# SPI_Stuff.net
KiCad netlist of a schematic drawn in Altium Designer
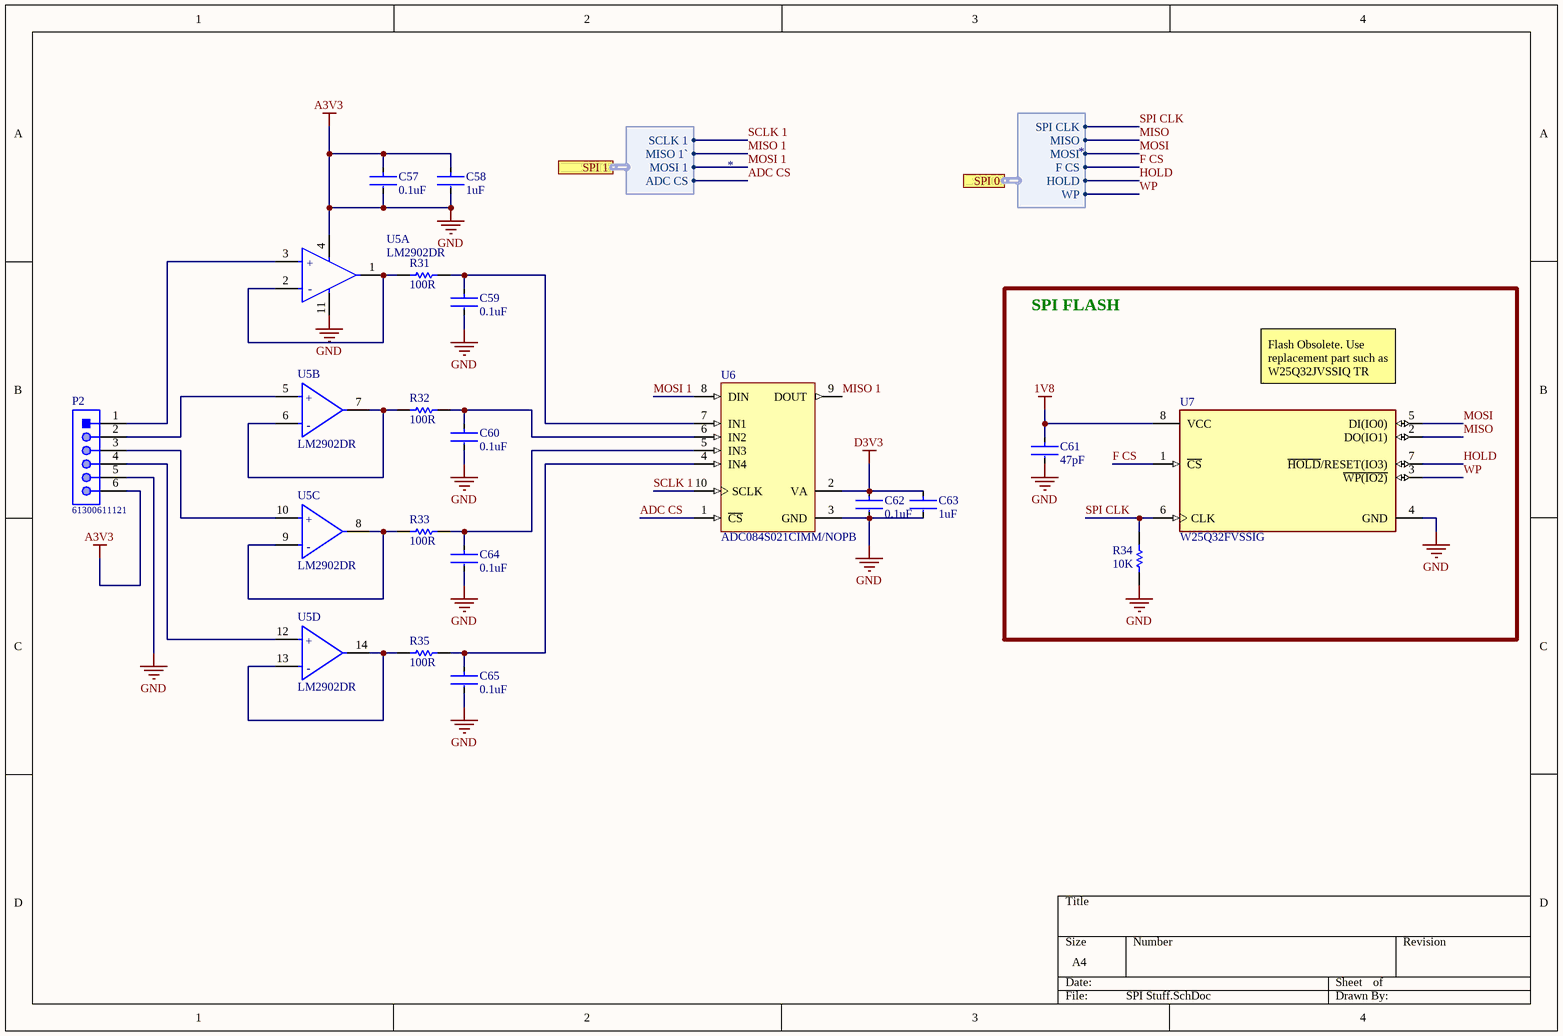
[diagram p0: SPI Stuff.SchDoc]

(export (version "E")
  (design (tool "Eeschema 10.0.6"))
  (components
    (comp (ref "C57")
      (value "0.1uF")
      (footprint "FP-GRM15-MFG")
      (description "CAP CER 0.1UF 16V X7R 0402")
      (fields (field (name "MANUFACTURER PART NUMBER") "GRM155R71C104KA88D") (field (name "TOLERANCE") "10%"))
      (libsource (lib "Altium Content Vault") (part "236180d848d6139a670b325ea6854c9"))
    )
    (comp (ref "C58")
      (value "1uF")
      (footprint "FP-GRM15-MFG")
      (description "CAP CER 0.1UF 16V X7R 0402")
      (fields (field (name "MANUFACTURER PART NUMBER") "GRM155R71C104KA88D") (field (name "TOLERANCE") "10%"))
      (libsource (lib "Altium Content Vault") (part "236180d848d6139a670b325ea6854c9"))
    )
    (comp (ref "C59")
      (value "0.1uF")
      (footprint "FP-GRM15-MFG")
      (description "CAP CER 0.1UF 16V X7R 0402")
      (fields (field (name "MANUFACTURER PART NUMBER") "GRM155R71C104KA88D") (field (name "TOLERANCE") "10%"))
      (libsource (lib "Altium Content Vault") (part "236180d848d6139a670b325ea6854c9"))
    )
    (comp (ref "C60")
      (value "0.1uF")
      (footprint "FP-GRM15-MFG")
      (description "CAP CER 0.1UF 16V X7R 0402")
      (fields (field (name "MANUFACTURER PART NUMBER") "GRM155R71C104KA88D") (field (name "TOLERANCE") "10%"))
      (libsource (lib "Altium Content Vault") (part "236180d848d6139a670b325ea6854c9"))
    )
    (comp (ref "C61")
      (value "47pF")
      (footprint "FP-GRM15-MFG")
      (description "CAP CER 0.1UF 16V X7R 0402")
      (fields (field (name "MANUFACTURER PART NUMBER") "GRM155R71C104KA88D") (field (name "TOLERANCE") "10%"))
      (libsource (lib "Altium Content Vault") (part "236180d848d6139a670b325ea6854c9"))
    )
    (comp (ref "C62")
      (value "0.1uF")
      (footprint "FP-GRM15-MFG")
      (description "CAP CER 0.1UF 16V X7R 0402")
      (fields (field (name "MANUFACTURER PART NUMBER") "GRM155R71C104KA88D") (field (name "TOLERANCE") "10%"))
      (libsource (lib "Altium Content Vault") (part "236180d848d6139a670b325ea6854c9"))
    )
    (comp (ref "C63")
      (value "1uF")
      (footprint "FP-GRM15-MFG")
      (description "CAP CER 0.1UF 16V X7R 0402")
      (fields (field (name "MANUFACTURER PART NUMBER") "GRM155R71C104KA88D") (field (name "TOLERANCE") "10%"))
      (libsource (lib "Altium Content Vault") (part "236180d848d6139a670b325ea6854c9"))
    )
    (comp (ref "C64")
      (value "0.1uF")
      (footprint "FP-GRM15-MFG")
      (description "CAP CER 0.1UF 16V X7R 0402")
      (fields (field (name "MANUFACTURER PART NUMBER") "GRM155R71C104KA88D") (field (name "TOLERANCE") "10%"))
      (libsource (lib "Altium Content Vault") (part "236180d848d6139a670b325ea6854c9"))
    )
    (comp (ref "C65")
      (value "0.1uF")
      (footprint "FP-GRM15-MFG")
      (description "CAP CER 0.1UF 16V X7R 0402")
      (fields (field (name "MANUFACTURER PART NUMBER") "GRM155R71C104KA88D") (field (name "TOLERANCE") "10%"))
      (libsource (lib "Altium Content Vault") (part "236180d848d6139a670b325ea6854c9"))
    )
    (comp (ref "P2")
      (value "61300611121")
      (footprint "61300611121")
      (description "THT Vertical Pin Header WR-PHD, Pitch 2.54 mm, Single Row, 6 pins")
      (fields (field (name "MANUFACTURER") "Wurth Elektronik") (field (name "PUBLISHER") "WurthElektronik"))
      (libsource (lib "Altium Content Vault") (part "WE-CN-1P-M-R6"))
    )
    (comp (ref "R31")
      (value "100R")
      (footprint "RESC1005X40X25LL05T05")
      (description "Chip Resistor, 0 Ohm, 0.1 W, -55 to 155 degC, 0402 (1005 Metric), RoHS, Tape and Reel")
      (fields (field (name "MANUFACTURER") "Panasonic") (field (name "TOLERANCE") "5%"))
      (libsource (lib "Altium Content Vault") (part "RES-2"))
    )
    (comp (ref "R32")
      (value "100R")
      (footprint "RESC1005X40X25LL05T05")
      (description "Chip Resistor, 0 Ohm, 0.1 W, -55 to 155 degC, 0402 (1005 Metric), RoHS, Tape and Reel")
      (fields (field (name "MANUFACTURER") "Panasonic") (field (name "TOLERANCE") "5%"))
      (libsource (lib "Altium Content Vault") (part "RES-2"))
    )
    (comp (ref "R33")
      (value "100R")
      (footprint "RESC1005X40X25LL05T05")
      (description "Chip Resistor, 0 Ohm, 0.1 W, -55 to 155 degC, 0402 (1005 Metric), RoHS, Tape and Reel")
      (fields (field (name "MANUFACTURER") "Panasonic") (field (name "TOLERANCE") "5%"))
      (libsource (lib "Altium Content Vault") (part "RES-2"))
    )
    (comp (ref "R34")
      (value "10K")
      (footprint "RESC1005X40X25LL05T05")
      (description "Chip Resistor, 0 Ohm, 0.1 W, -55 to 155 degC, 0402 (1005 Metric), RoHS, Tape and Reel")
      (fields (field (name "MANUFACTURER") "Panasonic") (field (name "TOLERANCE") "5%"))
      (libsource (lib "Altium Content Vault") (part "RES-2"))
    )
    (comp (ref "R35")
      (value "100R")
      (footprint "RESC1005X40X25LL05T05")
      (description "Chip Resistor, 0 Ohm, 0.1 W, -55 to 155 degC, 0402 (1005 Metric), RoHS, Tape and Reel")
      (fields (field (name "MANUFACTURER") "Panasonic") (field (name "TOLERANCE") "5%"))
      (libsource (lib "Altium Content Vault") (part "RES-2"))
    )
    (comp (ref "U5")
      (value "LM2902DR")
      (footprint "FP-D0014A-IPC_A")
      (description "IC OPAMP GP 4 CIRCUIT 14SOIC")
      (libsource (lib "Altium Content Vault") (part "b02d0cb41c0d90ddc6f34c0e90b5c12"))
    )
    (comp (ref "U6")
      (value "ADC084S021CIMM/NOPB")
      (footprint "MUB10A_N")
      (description "4 Channel, 50 kSPS to 200 kSPS, 8-Bit A/D Converter, 10-pin Mini SOIC, Pb-Free")
      (fields (field (name "MANUFACTURER") "National Semiconductor"))
      (libsource (lib "Altium Content Vault") (part "CON-ADC-ADC104S101CIMM"))
    )
    (comp (ref "U7")
      (value "W25Q32FVSSIG")
      (footprint "FP-SS-MFG")
      (description "IC FLASH 32M SPI 104MHZ 8SOIC")
      (fields
        (field (name "MANUFACTURER") "Winbond")
        (field (name "OCTOPART") "https://octopart.com/w25q32fvssig-winbond-23896462")
      )
      (libsource (lib "Altium Content Vault") (part "4804fbe011262506d6ec6a9051036b0"))
    )
  )
  (nets
    (net (code "2") (name "/ADC CS") (class "Default")
      (node (ref "U6") (pin "1") (pinfunction "~{CS}_1") (pintype "input"))
    )
    (net (code "3") (name "/F CS") (class "Default")
      (node (ref "U7") (pin "1") (pinfunction "~{CS}_1") (pintype "input"))
    )
    (net (code "4") (name "/HOLD") (class "Default")
      (node (ref "U7") (pin "7") (pinfunction "~{HOLD}/RESET(IO3)_7") (pintype "bidirectional"))
    )
    (net (code "5") (name "/MISO") (class "Default")
      (node (ref "U7") (pin "2") (pinfunction "DO(IO1)_2") (pintype "bidirectional"))
    )
    (net (code "6") (name "/MISO 1") (class "Default")
      (node (ref "U6") (pin "9") (pinfunction "DOUT_9") (pintype "output"))
    )
    (net (code "7") (name "/MOSI") (class "Default")
      (node (ref "U7") (pin "5") (pinfunction "DI(IO0)_5") (pintype "bidirectional"))
    )
    (net (code "8") (name "/MOSI 1") (class "Default")
      (node (ref "U6") (pin "8") (pinfunction "DIN_8") (pintype "input"))
    )
    (net (code "9") (name "/SCLK 1") (class "Default")
      (node (ref "U6") (pin "10") (pinfunction "SCLK_10") (pintype "input"))
    )
    (net (code "10") (name "/SPI CLK") (class "Default")
      (node (ref "R34") (pin "2") (pinfunction "2_2") (pintype "passive"))
      (node (ref "U7") (pin "6") (pinfunction "CLK_6") (pintype "input"))
    )
    (net (code "11") (name "/WP") (class "Default")
      (node (ref "U7") (pin "3") (pinfunction "~{WP(IO2)}_3") (pintype "bidirectional"))
    )
    (net (code "13") (name "1V8") (class "Default")
      (node (ref "C61") (pin "2") (pinfunction "2_2") (pintype "passive"))
      (node (ref "U7") (pin "8") (pinfunction "VCC_8") (pintype "power_in"))
    )
    (net (code "14") (name "A3V3") (class "Default")
      (node (ref "C57") (pin "1") (pinfunction "1_1") (pintype "passive"))
      (node (ref "C57") (pin "2") (pinfunction "2_2") (pintype "passive"))
      (node (ref "C58") (pin "1") (pinfunction "1_1") (pintype "passive"))
      (node (ref "C58") (pin "2") (pinfunction "2_2") (pintype "passive"))
      (node (ref "C59") (pin "1") (pinfunction "1_1") (pintype "passive"))
      (node (ref "C60") (pin "1") (pinfunction "1_1") (pintype "passive"))
      (node (ref "C61") (pin "1") (pinfunction "1_1") (pintype "passive"))
      (node (ref "C62") (pin "1") (pinfunction "1_1") (pintype "passive"))
      (node (ref "C63") (pin "1") (pinfunction "1_1") (pintype "passive"))
      (node (ref "C64") (pin "1") (pinfunction "1_1") (pintype "passive"))
      (node (ref "C65") (pin "1") (pinfunction "1_1") (pintype "passive"))
      (node (ref "P2") (pin "5") (pinfunction "5_5") (pintype "passive"))
      (node (ref "P2") (pin "6") (pinfunction "6_6") (pintype "passive"))
      (node (ref "R34") (pin "1") (pinfunction "1_1") (pintype "passive"))
      (node (ref "U5") (pin "11") (pinfunction "GND_11") (pintype "power_in"))
      (node (ref "U5") (pin "4") (pinfunction "VCC_4") (pintype "power_in"))
      (node (ref "U6") (pin "3") (pinfunction "GND_3") (pintype "power_in"))
      (node (ref "U7") (pin "4") (pinfunction "GND_4") (pintype "power_in"))
    )
    (net (code "15") (name "D3V3") (class "Default")
      (node (ref "C62") (pin "2") (pinfunction "2_2") (pintype "passive"))
      (node (ref "C63") (pin "2") (pinfunction "2_2") (pintype "passive"))
      (node (ref "U6") (pin "2") (pinfunction "VA_2") (pintype "power_in"))
    )
    (net (code "16") (name "Net-(U5A-1IN+)") (class "Default")
      (node (ref "P2") (pin "1") (pinfunction "1_1") (pintype "passive"))
      (node (ref "U5") (pin "3") (pinfunction "1IN+_3") (pintype "tri_state"))
    )
    (net (code "17") (name "Net-(U5A-1IN-)") (class "Default")
      (node (ref "R31") (pin "2") (pinfunction "2_2") (pintype "passive"))
      (node (ref "U5") (pin "1") (pinfunction "1OUT_1") (pintype "passive"))
      (node (ref "U5") (pin "2") (pinfunction "1IN-_2") (pintype "tri_state"))
    )
    (net (code "18") (name "Net-(U5B-2IN+)") (class "Default")
      (node (ref "P2") (pin "2") (pinfunction "2_2") (pintype "passive"))
      (node (ref "U5") (pin "5") (pinfunction "2IN+_5") (pintype "tri_state"))
    )
    (net (code "19") (name "Net-(U5B-2IN-)") (class "Default")
      (node (ref "R32") (pin "2") (pinfunction "2_2") (pintype "passive"))
      (node (ref "U5") (pin "6") (pinfunction "2IN-_6") (pintype "tri_state"))
      (node (ref "U5") (pin "7") (pinfunction "2OUT_7") (pintype "passive"))
    )
    (net (code "20") (name "Net-(U5C-3IN+)") (class "Default")
      (node (ref "P2") (pin "3") (pinfunction "3_3") (pintype "passive"))
      (node (ref "U5") (pin "10") (pinfunction "3IN+_10") (pintype "tri_state"))
    )
    (net (code "21") (name "Net-(U5C-3IN-)") (class "Default")
      (node (ref "R33") (pin "2") (pinfunction "2_2") (pintype "passive"))
      (node (ref "U5") (pin "8") (pinfunction "3OUT_8") (pintype "passive"))
      (node (ref "U5") (pin "9") (pinfunction "3IN-_9") (pintype "tri_state"))
    )
    (net (code "22") (name "Net-(U5D-4IN+)") (class "Default")
      (node (ref "P2") (pin "4") (pinfunction "4_4") (pintype "passive"))
      (node (ref "U5") (pin "12") (pinfunction "4IN+_12") (pintype "tri_state"))
    )
    (net (code "23") (name "Net-(U5D-4IN-)") (class "Default")
      (node (ref "R35") (pin "2") (pinfunction "2_2") (pintype "passive"))
      (node (ref "U5") (pin "13") (pinfunction "4IN-_13") (pintype "tri_state"))
      (node (ref "U5") (pin "14") (pinfunction "4OUT_14") (pintype "passive"))
    )
    (net (code "24") (name "Net-(U6-IN1)") (class "Default")
      (node (ref "C59") (pin "2") (pinfunction "2_2") (pintype "passive"))
      (node (ref "R31") (pin "1") (pinfunction "1_1") (pintype "passive"))
      (node (ref "U6") (pin "7") (pinfunction "IN1_7") (pintype "input"))
    )
    (net (code "25") (name "Net-(U6-IN2)") (class "Default")
      (node (ref "C60") (pin "2") (pinfunction "2_2") (pintype "passive"))
      (node (ref "R32") (pin "1") (pinfunction "1_1") (pintype "passive"))
      (node (ref "U6") (pin "6") (pinfunction "IN2_6") (pintype "input"))
    )
    (net (code "26") (name "Net-(U6-IN3)") (class "Default")
      (node (ref "C64") (pin "2") (pinfunction "2_2") (pintype "passive"))
      (node (ref "R33") (pin "1") (pinfunction "1_1") (pintype "passive"))
      (node (ref "U6") (pin "5") (pinfunction "IN3_5") (pintype "input"))
    )
    (net (code "27") (name "Net-(U6-IN4)") (class "Default")
      (node (ref "C65") (pin "2") (pinfunction "2_2") (pintype "passive"))
      (node (ref "R35") (pin "1") (pinfunction "1_1") (pintype "passive"))
      (node (ref "U6") (pin "4") (pinfunction "IN4_4") (pintype "input"))
    )
  )
)
